# Sensing_-_Voltage.net
KiCad netlist of a schematic drawn in Altium Designer
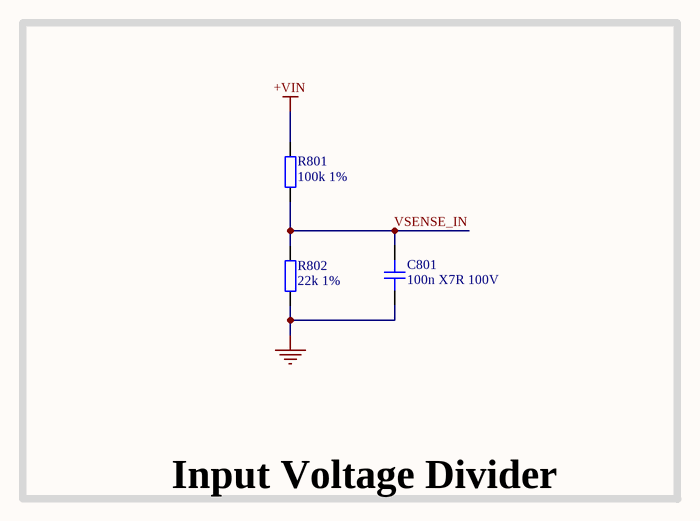
[diagram p0: Sensing - Voltage.SchDoc]

(export (version "E")
  (design (tool "Eeschema 10.0.6"))
  (components
    (comp (ref "C801")
      (value "100n X7R 100V")
      (footprint "CAP_0603")
      (description "Capacitor SMD 0603")
      (fields
        (field (name "MANUFACTURER") "CCTC")
        (field (name "MANUFACTURER PART NUMBER") "TCC0603X7R104K101CT")
      )
      (libsource (lib "Schematic-Lib-PhilsLab") (part "CAP_0603"))
    )
    (comp (ref "R801")
      (value "100k 1%")
      (footprint "RES_0603")
      (description "Resistor SMD 0603")
      (fields
        (field (name "MANUFACTURER") "Vishay Intertech")
        (field (name "MANUFACTURER PART NUMBER") "MCT06030C1003FP500")
      )
      (libsource (lib "Schematic-Lib-PhilsLab") (part "RES_0603"))
    )
    (comp (ref "R802")
      (value "22k 1%")
      (footprint "RES_0603")
      (description "Resistor SMD 0603")
      (fields
        (field (name "MANUFACTURER") "Vishay Intertech")
        (field (name "MANUFACTURER PART NUMBER") "CRCW060322K0FKEA")
      )
      (libsource (lib "Schematic-Lib-PhilsLab") (part "RES_0603"))
    )
  )
  (nets
    (net (code "1") (name "+VIN") (class "Default")
      (node (ref "R801") (pin "2") (pinfunction "2_2") (pintype "passive"))
    )
    (net (code "2") (name "/VSENSE_IN") (class "Default")
      (node (ref "C801") (pin "2") (pinfunction "2_2") (pintype "passive"))
      (node (ref "R801") (pin "1") (pinfunction "1_1") (pintype "passive"))
      (node (ref "R802") (pin "2") (pinfunction "2_2") (pintype "passive"))
    )
    (net (code "3") (name "GND") (class "Default")
      (node (ref "C801") (pin "1") (pinfunction "1_1") (pintype "passive"))
      (node (ref "R802") (pin "1") (pinfunction "1_1") (pintype "passive"))
    )
  )
)
